# MAPE-CUN-Large-016.net
KiCad netlist of a schematic drawn in EAGLE
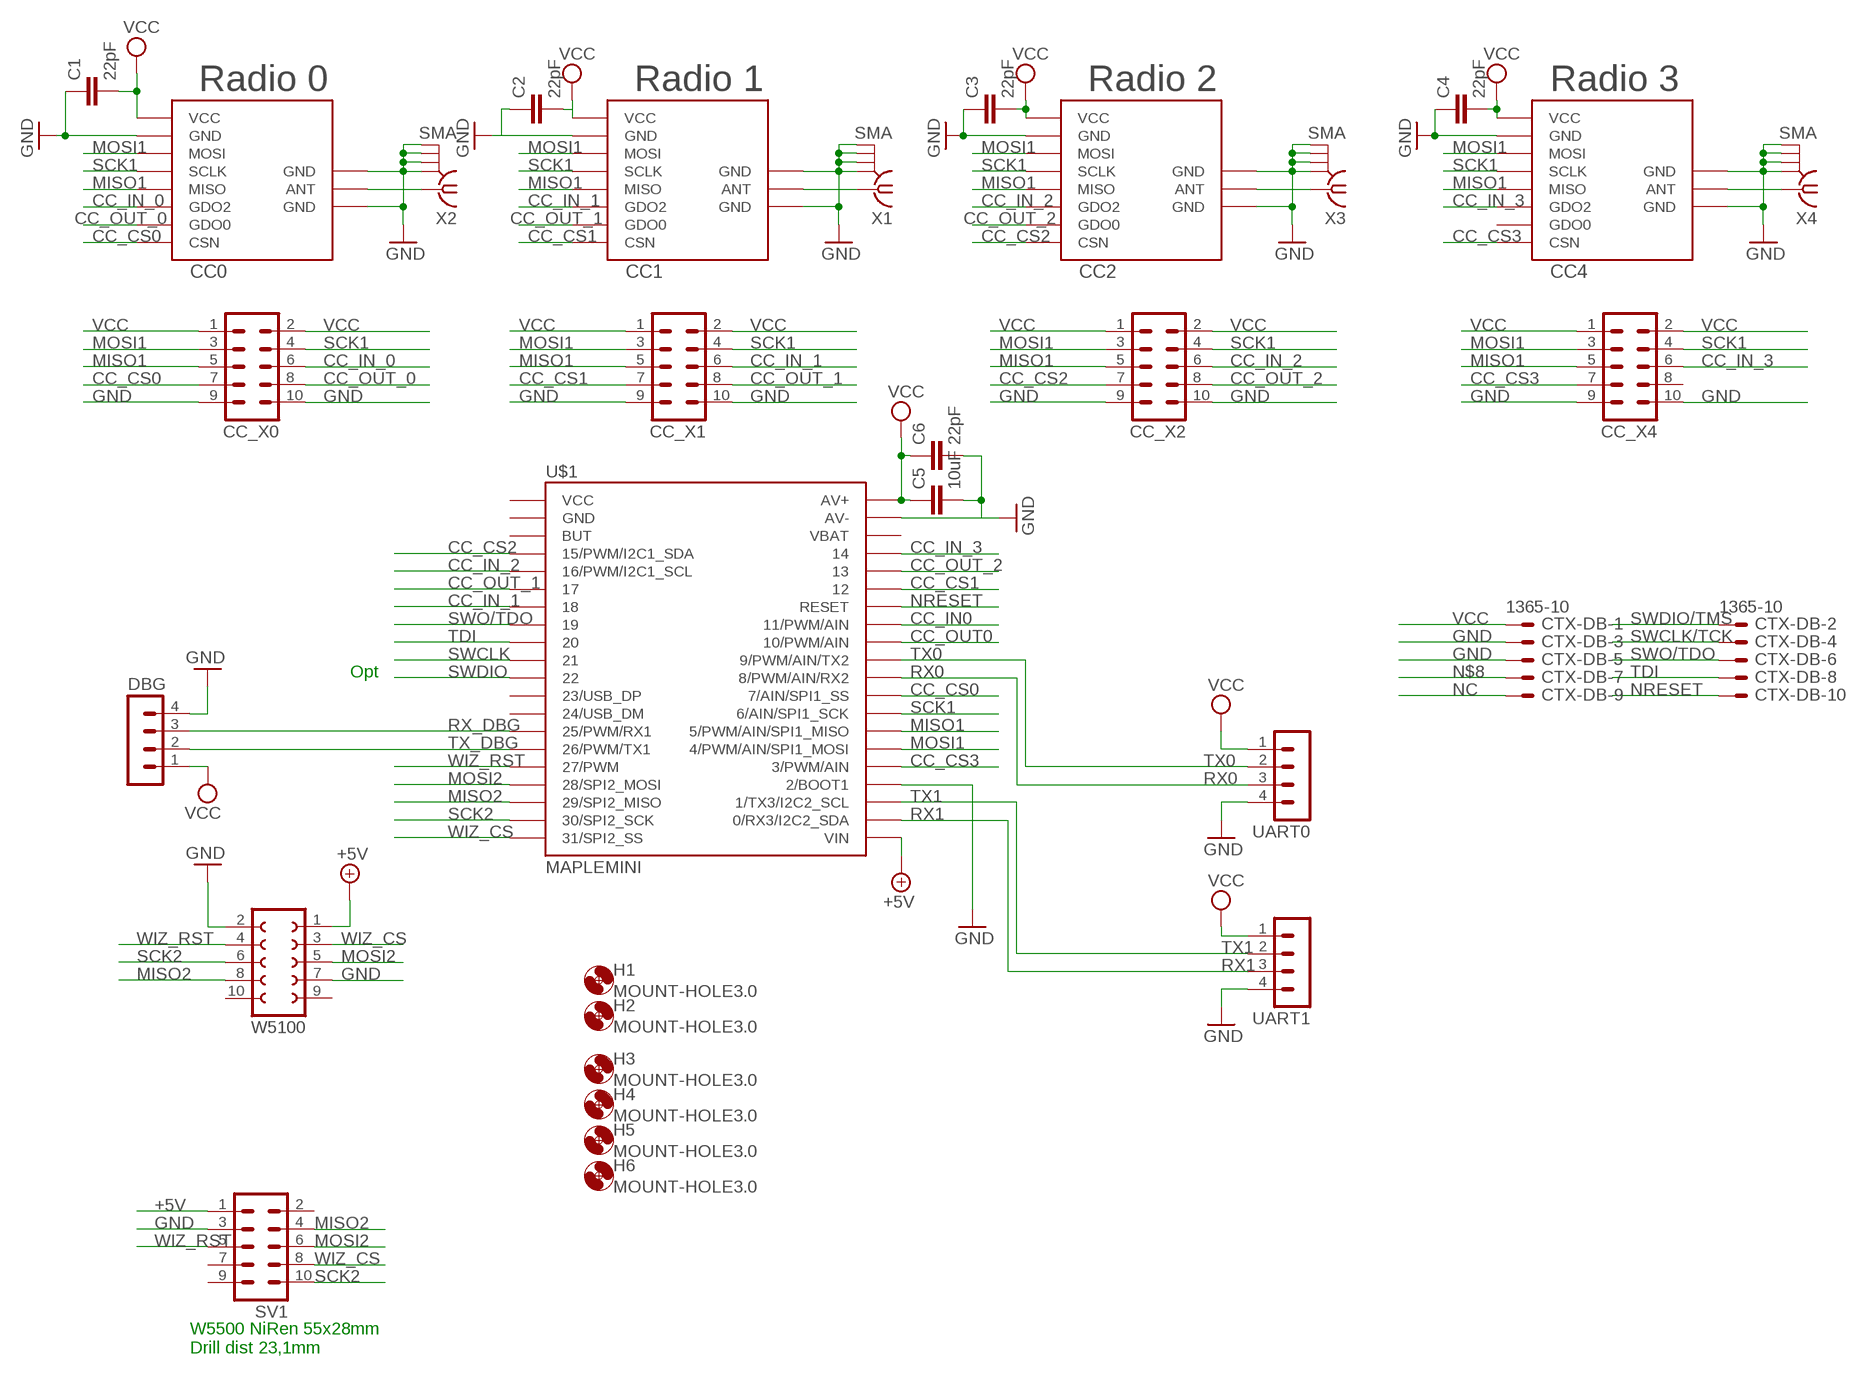
[diagram p0: schematic, sheet 1]

(export (version "E")
  (design (tool "Eeschema 10.0.6"))
  (components
    (comp (ref "C1")
      (value "22pF")
      (footprint "eagle-import:C0805")
      (libsource (lib "eagle-import") (part "C-EUC0805"))
    )
    (comp (ref "C2")
      (value "22pF")
      (footprint "eagle-import:C0805")
      (libsource (lib "eagle-import") (part "C-EUC0805"))
    )
    (comp (ref "C3")
      (value "22pF")
      (footprint "eagle-import:C0805")
      (libsource (lib "eagle-import") (part "C-EUC0805"))
    )
    (comp (ref "C4")
      (value "22pF")
      (footprint "eagle-import:C0805")
      (libsource (lib "eagle-import") (part "C-EUC0805"))
    )
    (comp (ref "C5")
      (value "10uF")
      (footprint "eagle-import:C1210")
      (libsource (lib "eagle-import") (part "C-EUC1210"))
    )
    (comp (ref "C6")
      (value "22pF")
      (footprint "eagle-import:C0805")
      (libsource (lib "eagle-import") (part "C-EUC0805"))
    )
    (comp (ref "CC0")
      (value "CC1101_MODULE1SMD")
      (footprint "eagle-import:CC1101_MODULE1_SMD")
      (libsource (lib "eagle-import") (part "CC1101_MODULE1SMD"))
    )
    (comp (ref "CC1")
      (value "CC1101_MODULE1SMD")
      (footprint "eagle-import:CC1101_MODULE1_SMD")
      (libsource (lib "eagle-import") (part "CC1101_MODULE1SMD"))
    )
    (comp (ref "CC2")
      (value "CC1101_MODULE1SMD")
      (footprint "eagle-import:CC1101_MODULE1_SMD")
      (libsource (lib "eagle-import") (part "CC1101_MODULE1SMD"))
    )
    (comp (ref "CC4")
      (value "CC1101_MODULE1SMD")
      (footprint "eagle-import:CC1101_MODULE1_SMD")
      (libsource (lib "eagle-import") (part "CC1101_MODULE1SMD"))
    )
    (comp (ref "CC_X0")
      (value "MA05-2")
      (footprint "eagle-import:MA05-2")
      (libsource (lib "eagle-import") (part "MA05-2"))
    )
    (comp (ref "CC_X1")
      (value "MA05-2")
      (footprint "eagle-import:MA05-2")
      (libsource (lib "eagle-import") (part "MA05-2"))
    )
    (comp (ref "CC_X2")
      (value "MA05-2")
      (footprint "eagle-import:MA05-2")
      (libsource (lib "eagle-import") (part "MA05-2"))
    )
    (comp (ref "CC_X4")
      (value "MA05-2")
      (footprint "eagle-import:MA05-2")
      (libsource (lib "eagle-import") (part "MA05-2"))
    )
    (comp (ref "CTX-DB")
      (value "1365-10")
      (footprint "eagle-import:1365-10")
      (libsource (lib "eagle-import") (part "1365-10"))
    )
    (comp (ref "DBG")
      (value "MA04-1")
      (footprint "eagle-import:MA04-1")
      (libsource (lib "eagle-import") (part "MA04-1"))
    )
    (comp (ref "H1")
      (value "MOUNT-HOLE3.0")
      (footprint "eagle-import:3,0")
      (libsource (lib "eagle-import") (part "MOUNT-HOLE3.0"))
    )
    (comp (ref "H2")
      (value "MOUNT-HOLE3.0")
      (footprint "eagle-import:3,0")
      (libsource (lib "eagle-import") (part "MOUNT-HOLE3.0"))
    )
    (comp (ref "H3")
      (value "MOUNT-HOLE3.0")
      (footprint "eagle-import:3,0")
      (libsource (lib "eagle-import") (part "MOUNT-HOLE3.0"))
    )
    (comp (ref "H4")
      (value "MOUNT-HOLE3.0")
      (footprint "eagle-import:3,0")
      (libsource (lib "eagle-import") (part "MOUNT-HOLE3.0"))
    )
    (comp (ref "H5")
      (value "MOUNT-HOLE3.0")
      (footprint "eagle-import:3,0")
      (libsource (lib "eagle-import") (part "MOUNT-HOLE3.0"))
    )
    (comp (ref "H6")
      (value "MOUNT-HOLE3.0")
      (footprint "eagle-import:3,0")
      (libsource (lib "eagle-import") (part "MOUNT-HOLE3.0"))
    )
    (comp (ref "SV1")
      (value "MA05-2")
      (footprint "eagle-import:MA05-2")
      (libsource (lib "eagle-import") (part "MA05-2"))
    )
    (comp (ref "U$1")
      (value "MAPLEMINI")
      (footprint "eagle-import:20-DIP")
      (libsource (lib "eagle-import") (part "MAPLEMINI"))
    )
    (comp (ref "UART0")
      (value "MA04-1")
      (footprint "eagle-import:MA04-1")
      (libsource (lib "eagle-import") (part "MA04-1"))
    )
    (comp (ref "UART1")
      (value "MA04-1")
      (footprint "eagle-import:MA04-1")
      (libsource (lib "eagle-import") (part "MA04-1"))
    )
    (comp (ref "W5100")
      (value "FE05-2")
      (footprint "eagle-import:FE05-2")
      (libsource (lib "eagle-import") (part "FE05-2"))
    )
    (comp (ref "X1")
      (value "SMA")
      (footprint "eagle-import:SMA")
      (libsource (lib "eagle-import") (part "SMA"))
    )
    (comp (ref "X2")
      (value "SMA")
      (footprint "eagle-import:SMA")
      (libsource (lib "eagle-import") (part "SMA"))
    )
    (comp (ref "X3")
      (value "SMA")
      (footprint "eagle-import:SMA")
      (libsource (lib "eagle-import") (part "SMA"))
    )
    (comp (ref "X4")
      (value "SMA")
      (footprint "eagle-import:SMA")
      (libsource (lib "eagle-import") (part "SMA"))
    )
  )
  (nets
    (net (code "1") (name "+5V") (class "Default")
      (node (ref "SV1") (pin "1") (pinfunction "1_1") (pintype "passive"))
      (node (ref "U$1") (pin "21") (pinfunction "VIN_21") (pintype "bidirectional"))
      (node (ref "W5100") (pin "1") (pinfunction "1_1") (pintype "passive"))
    )
    (net (code "2") (name "/CC_CS0") (class "Default")
      (node (ref "CC0") (pin "CSN") (pinfunction "CSN_CSN") (pintype "bidirectional"))
      (node (ref "CC_X0") (pin "7") (pinfunction "7_7") (pintype "passive"))
      (node (ref "U$1") (pin "29") (pinfunction "7/AIN/SPI1_SS_29") (pintype "bidirectional"))
    )
    (net (code "3") (name "/CC_CS1") (class "Default")
      (node (ref "CC1") (pin "CSN") (pinfunction "CSN_CSN") (pintype "bidirectional"))
      (node (ref "CC_X1") (pin "7") (pinfunction "7_7") (pintype "passive"))
      (node (ref "U$1") (pin "35") (pinfunction "12_35") (pintype "bidirectional"))
    )
    (net (code "4") (name "/CC_CS2") (class "Default")
      (node (ref "CC2") (pin "CSN") (pinfunction "CSN_CSN") (pintype "bidirectional"))
      (node (ref "CC_X2") (pin "7") (pinfunction "7_7") (pintype "passive"))
      (node (ref "U$1") (pin "4") (pinfunction "15/PWM/I2C1_SDA_4") (pintype "bidirectional"))
    )
    (net (code "5") (name "/CC_CS3") (class "Default")
      (node (ref "CC4") (pin "CSN") (pinfunction "CSN_CSN") (pintype "bidirectional"))
      (node (ref "CC_X4") (pin "7") (pinfunction "7_7") (pintype "passive"))
      (node (ref "U$1") (pin "25") (pinfunction "3/PWM/AIN_25") (pintype "bidirectional"))
    )
    (net (code "6") (name "/CC_IN0") (class "Default")
      (node (ref "U$1") (pin "33") (pinfunction "11/PWM/AIN_33") (pintype "bidirectional"))
    )
    (net (code "7") (name "/CC_IN_0") (class "Default")
      (node (ref "CC0") (pin "GDO2") (pinfunction "GDO2_GDO2") (pintype "bidirectional"))
      (node (ref "CC_X0") (pin "6") (pinfunction "6_6") (pintype "passive"))
    )
    (net (code "8") (name "/CC_IN_1") (class "Default")
      (node (ref "CC1") (pin "GDO2") (pinfunction "GDO2_GDO2") (pintype "bidirectional"))
      (node (ref "CC_X1") (pin "6") (pinfunction "6_6") (pintype "passive"))
      (node (ref "U$1") (pin "7") (pinfunction "18_7") (pintype "bidirectional"))
    )
    (net (code "9") (name "/CC_IN_2") (class "Default")
      (node (ref "CC2") (pin "GDO2") (pinfunction "GDO2_GDO2") (pintype "bidirectional"))
      (node (ref "CC_X2") (pin "6") (pinfunction "6_6") (pintype "passive"))
      (node (ref "U$1") (pin "5") (pinfunction "16/PWM/I2C1_SCL_5") (pintype "bidirectional"))
    )
    (net (code "10") (name "/CC_IN_3") (class "Default")
      (node (ref "CC4") (pin "GDO2") (pinfunction "GDO2_GDO2") (pintype "bidirectional"))
      (node (ref "CC_X4") (pin "6") (pinfunction "6_6") (pintype "passive"))
      (node (ref "U$1") (pin "37") (pinfunction "14_37") (pintype "bidirectional"))
    )
    (net (code "11") (name "/CC_OUT0") (class "Default")
      (node (ref "U$1") (pin "32") (pinfunction "10/PWM/AIN_32") (pintype "bidirectional"))
    )
    (net (code "12") (name "/CC_OUT_0") (class "Default")
      (node (ref "CC0") (pin "GDO0") (pinfunction "GDO0_GDO0") (pintype "bidirectional"))
      (node (ref "CC_X0") (pin "8") (pinfunction "8_8") (pintype "passive"))
    )
    (net (code "13") (name "/CC_OUT_1") (class "Default")
      (node (ref "CC1") (pin "GDO0") (pinfunction "GDO0_GDO0") (pintype "bidirectional"))
      (node (ref "CC_X1") (pin "8") (pinfunction "8_8") (pintype "passive"))
      (node (ref "U$1") (pin "6") (pinfunction "17_6") (pintype "bidirectional"))
    )
    (net (code "14") (name "/CC_OUT_2") (class "Default")
      (node (ref "CC2") (pin "GDO0") (pinfunction "GDO0_GDO0") (pintype "bidirectional"))
      (node (ref "CC_X2") (pin "8") (pinfunction "8_8") (pintype "passive"))
      (node (ref "U$1") (pin "36") (pinfunction "13_36") (pintype "bidirectional"))
    )
    (net (code "15") (name "/MISO1") (class "Default")
      (node (ref "CC0") (pin "MISO") (pinfunction "MISO_MISO") (pintype "bidirectional"))
      (node (ref "CC1") (pin "MISO") (pinfunction "MISO_MISO") (pintype "bidirectional"))
      (node (ref "CC2") (pin "MISO") (pinfunction "MISO_MISO") (pintype "bidirectional"))
      (node (ref "CC4") (pin "MISO") (pinfunction "MISO_MISO") (pintype "bidirectional"))
      (node (ref "CC_X0") (pin "5") (pinfunction "5_5") (pintype "passive"))
      (node (ref "CC_X1") (pin "5") (pinfunction "5_5") (pintype "passive"))
      (node (ref "CC_X2") (pin "5") (pinfunction "5_5") (pintype "passive"))
      (node (ref "CC_X4") (pin "5") (pinfunction "5_5") (pintype "passive"))
      (node (ref "U$1") (pin "27") (pinfunction "5/PWM/AIN/SPI1_MISO_27") (pintype "bidirectional"))
    )
    (net (code "16") (name "/MISO2") (class "Default")
      (node (ref "SV1") (pin "4") (pinfunction "4_4") (pintype "passive"))
      (node (ref "U$1") (pin "18") (pinfunction "29/SPI2_MISO_18") (pintype "bidirectional"))
      (node (ref "W5100") (pin "8") (pinfunction "8_8") (pintype "passive"))
    )
    (net (code "17") (name "/MOSI1") (class "Default")
      (node (ref "CC0") (pin "MOSI") (pinfunction "MOSI_MOSI") (pintype "bidirectional"))
      (node (ref "CC1") (pin "MOSI") (pinfunction "MOSI_MOSI") (pintype "bidirectional"))
      (node (ref "CC2") (pin "MOSI") (pinfunction "MOSI_MOSI") (pintype "bidirectional"))
      (node (ref "CC4") (pin "MOSI") (pinfunction "MOSI_MOSI") (pintype "bidirectional"))
      (node (ref "CC_X0") (pin "3") (pinfunction "3_3") (pintype "passive"))
      (node (ref "CC_X1") (pin "3") (pinfunction "3_3") (pintype "passive"))
      (node (ref "CC_X2") (pin "3") (pinfunction "3_3") (pintype "passive"))
      (node (ref "CC_X4") (pin "3") (pinfunction "3_3") (pintype "passive"))
      (node (ref "U$1") (pin "26") (pinfunction "4/PWM/AIN/SPI1_MOSI_26") (pintype "bidirectional"))
    )
    (net (code "18") (name "/MOSI2") (class "Default")
      (node (ref "SV1") (pin "6") (pinfunction "6_6") (pintype "passive"))
      (node (ref "U$1") (pin "17") (pinfunction "28/SPI2_MOSI_17") (pintype "bidirectional"))
      (node (ref "W5100") (pin "5") (pinfunction "5_5") (pintype "passive"))
    )
    (net (code "19") (name "/N$8") (class "Default")
      (node (ref "CTX-DB") (pin "7") (pinfunction "S_7") (pintype "passive"))
    )
    (net (code "20") (name "/NC") (class "Default")
      (node (ref "CTX-DB") (pin "9") (pinfunction "S_9") (pintype "passive"))
    )
    (net (code "21") (name "/NRESET") (class "Default")
      (node (ref "CTX-DB") (pin "10") (pinfunction "S_10") (pintype "passive"))
      (node (ref "U$1") (pin "34") (pinfunction "RESET_34") (pintype "bidirectional"))
    )
    (net (code "22") (name "/RX0") (class "Default")
      (node (ref "U$1") (pin "30") (pinfunction "8/PWM/AIN/RX2_30") (pintype "bidirectional"))
      (node (ref "UART0") (pin "3") (pinfunction "3_3") (pintype "passive"))
    )
    (net (code "23") (name "/RX1") (class "Default")
      (node (ref "U$1") (pin "22") (pinfunction "0/RX3/I2C2_SDA_22") (pintype "bidirectional"))
      (node (ref "UART1") (pin "3") (pinfunction "3_3") (pintype "passive"))
    )
    (net (code "24") (name "/RX_DBG") (class "Default")
      (node (ref "DBG") (pin "3") (pinfunction "3_3") (pintype "passive"))
      (node (ref "U$1") (pin "14") (pinfunction "25/PWM/RX1_14") (pintype "bidirectional"))
    )
    (net (code "25") (name "/SCK1") (class "Default")
      (node (ref "CC0") (pin "SCLK") (pinfunction "SCLK_SCLK") (pintype "bidirectional"))
      (node (ref "CC1") (pin "SCLK") (pinfunction "SCLK_SCLK") (pintype "bidirectional"))
      (node (ref "CC2") (pin "SCLK") (pinfunction "SCLK_SCLK") (pintype "bidirectional"))
      (node (ref "CC4") (pin "SCLK") (pinfunction "SCLK_SCLK") (pintype "bidirectional"))
      (node (ref "CC_X0") (pin "4") (pinfunction "4_4") (pintype "passive"))
      (node (ref "CC_X1") (pin "4") (pinfunction "4_4") (pintype "passive"))
      (node (ref "CC_X2") (pin "4") (pinfunction "4_4") (pintype "passive"))
      (node (ref "CC_X4") (pin "4") (pinfunction "4_4") (pintype "passive"))
      (node (ref "U$1") (pin "28") (pinfunction "6/AIN/SPI1_SCK_28") (pintype "bidirectional"))
    )
    (net (code "26") (name "/SCK2") (class "Default")
      (node (ref "SV1") (pin "10") (pinfunction "10_10") (pintype "passive"))
      (node (ref "U$1") (pin "19") (pinfunction "30/SPI2_SCK_19") (pintype "bidirectional"))
      (node (ref "W5100") (pin "6") (pinfunction "6_6") (pintype "passive"))
    )
    (net (code "27") (name "/SWCLK") (class "Default")
      (node (ref "U$1") (pin "10") (pinfunction "21_10") (pintype "bidirectional"))
    )
    (net (code "28") (name "/SWCLK{slash}TCK") (class "Default")
      (node (ref "CTX-DB") (pin "4") (pinfunction "S_4") (pintype "passive"))
    )
    (net (code "29") (name "/SWDIO") (class "Default")
      (node (ref "U$1") (pin "11") (pinfunction "22_11") (pintype "bidirectional"))
    )
    (net (code "30") (name "/SWDIO{slash}TMS") (class "Default")
      (node (ref "CTX-DB") (pin "2") (pinfunction "S_2") (pintype "passive"))
    )
    (net (code "31") (name "/SWO{slash}TDO") (class "Default")
      (node (ref "CTX-DB") (pin "6") (pinfunction "S_6") (pintype "passive"))
      (node (ref "U$1") (pin "8") (pinfunction "19_8") (pintype "bidirectional"))
    )
    (net (code "32") (name "/TDI") (class "Default")
      (node (ref "CTX-DB") (pin "8") (pinfunction "S_8") (pintype "passive"))
      (node (ref "U$1") (pin "9") (pinfunction "20_9") (pintype "bidirectional"))
    )
    (net (code "33") (name "/TX0") (class "Default")
      (node (ref "U$1") (pin "31") (pinfunction "9/PWM/AIN/TX2_31") (pintype "bidirectional"))
      (node (ref "UART0") (pin "2") (pinfunction "2_2") (pintype "passive"))
    )
    (net (code "34") (name "/TX1") (class "Default")
      (node (ref "U$1") (pin "23") (pinfunction "1/TX3/I2C2_SCL_23") (pintype "bidirectional"))
      (node (ref "UART1") (pin "2") (pinfunction "2_2") (pintype "passive"))
    )
    (net (code "35") (name "/TX_DBG") (class "Default")
      (node (ref "DBG") (pin "2") (pinfunction "2_2") (pintype "passive"))
      (node (ref "U$1") (pin "15") (pinfunction "26/PWM/TX1_15") (pintype "bidirectional"))
    )
    (net (code "36") (name "/WIZ_CS") (class "Default")
      (node (ref "SV1") (pin "8") (pinfunction "8_8") (pintype "passive"))
      (node (ref "U$1") (pin "20") (pinfunction "31/SPI2_SS_20") (pintype "bidirectional"))
      (node (ref "W5100") (pin "3") (pinfunction "3_3") (pintype "passive"))
    )
    (net (code "37") (name "/WIZ_RST") (class "Default")
      (node (ref "SV1") (pin "5") (pinfunction "5_5") (pintype "passive"))
      (node (ref "U$1") (pin "16") (pinfunction "27/PWM_16") (pintype "bidirectional"))
      (node (ref "W5100") (pin "4") (pinfunction "4_4") (pintype "passive"))
    )
    (net (code "38") (name "GND") (class "Default")
      (node (ref "C1") (pin "1") (pinfunction "1_1") (pintype "passive"))
      (node (ref "C2") (pin "1") (pinfunction "1_1") (pintype "passive"))
      (node (ref "C3") (pin "1") (pinfunction "1_1") (pintype "passive"))
      (node (ref "C4") (pin "1") (pinfunction "1_1") (pintype "passive"))
      (node (ref "C5") (pin "2") (pinfunction "2_2") (pintype "passive"))
      (node (ref "C6") (pin "2") (pinfunction "2_2") (pintype "passive"))
      (node (ref "CC0") (pin "GND@0") (pinfunction "GND_GND@0") (pintype "power_in"))
      (node (ref "CC0") (pin "GND@1") (pinfunction "GND_GND@1") (pintype "power_in"))
      (node (ref "CC0") (pin "GND@2") (pinfunction "GND_GND@2") (pintype "power_in"))
      (node (ref "CC1") (pin "GND@0") (pinfunction "GND_GND@0") (pintype "power_in"))
      (node (ref "CC1") (pin "GND@1") (pinfunction "GND_GND@1") (pintype "power_in"))
      (node (ref "CC1") (pin "GND@2") (pinfunction "GND_GND@2") (pintype "power_in"))
      (node (ref "CC2") (pin "GND@0") (pinfunction "GND_GND@0") (pintype "power_in"))
      (node (ref "CC2") (pin "GND@1") (pinfunction "GND_GND@1") (pintype "power_in"))
      (node (ref "CC2") (pin "GND@2") (pinfunction "GND_GND@2") (pintype "power_in"))
      (node (ref "CC4") (pin "GND@0") (pinfunction "GND_GND@0") (pintype "power_in"))
      (node (ref "CC4") (pin "GND@1") (pinfunction "GND_GND@1") (pintype "power_in"))
      (node (ref "CC4") (pin "GND@2") (pinfunction "GND_GND@2") (pintype "power_in"))
      (node (ref "CC_X0") (pin "10") (pinfunction "10_10") (pintype "passive"))
      (node (ref "CC_X0") (pin "9") (pinfunction "9_9") (pintype "passive"))
      (node (ref "CC_X1") (pin "10") (pinfunction "10_10") (pintype "passive"))
      (node (ref "CC_X1") (pin "9") (pinfunction "9_9") (pintype "passive"))
      (node (ref "CC_X2") (pin "10") (pinfunction "10_10") (pintype "passive"))
      (node (ref "CC_X2") (pin "9") (pinfunction "9_9") (pintype "passive"))
      (node (ref "CC_X4") (pin "10") (pinfunction "10_10") (pintype "passive"))
      (node (ref "CC_X4") (pin "9") (pinfunction "9_9") (pintype "passive"))
      (node (ref "CTX-DB") (pin "3") (pinfunction "S_3") (pintype "passive"))
      (node (ref "CTX-DB") (pin "5") (pinfunction "S_5") (pintype "passive"))
      (node (ref "DBG") (pin "4") (pinfunction "4_4") (pintype "passive"))
      (node (ref "SV1") (pin "3") (pinfunction "3_3") (pintype "passive"))
      (node (ref "U$1") (pin "24") (pinfunction "2/BOOT1_24") (pintype "bidirectional"))
      (node (ref "U$1") (pin "39") (pinfunction "AV-_39") (pintype "bidirectional"))
      (node (ref "UART0") (pin "4") (pinfunction "4_4") (pintype "passive"))
      (node (ref "UART1") (pin "4") (pinfunction "4_4") (pintype "passive"))
      (node (ref "W5100") (pin "2") (pinfunction "2_2") (pintype "passive"))
      (node (ref "W5100") (pin "7") (pinfunction "7_7") (pintype "passive"))
      (node (ref "X1") (pin "GND@1") (pinfunction "2_GND@1") (pintype "passive"))
      (node (ref "X1") (pin "GND@2") (pinfunction "3_GND@2") (pintype "passive"))
      (node (ref "X1") (pin "GND@3") (pinfunction "4_GND@3") (pintype "passive"))
      (node (ref "X1") (pin "GND@4") (pinfunction "5_GND@4") (pintype "passive"))
      (node (ref "X2") (pin "GND@1") (pinfunction "2_GND@1") (pintype "passive"))
      (node (ref "X2") (pin "GND@2") (pinfunction "3_GND@2") (pintype "passive"))
      (node (ref "X2") (pin "GND@3") (pinfunction "4_GND@3") (pintype "passive"))
      (node (ref "X2") (pin "GND@4") (pinfunction "5_GND@4") (pintype "passive"))
      (node (ref "X3") (pin "GND@1") (pinfunction "2_GND@1") (pintype "passive"))
      (node (ref "X3") (pin "GND@2") (pinfunction "3_GND@2") (pintype "passive"))
      (node (ref "X3") (pin "GND@3") (pinfunction "4_GND@3") (pintype "passive"))
      (node (ref "X3") (pin "GND@4") (pinfunction "5_GND@4") (pintype "passive"))
      (node (ref "X4") (pin "GND@1") (pinfunction "2_GND@1") (pintype "passive"))
      (node (ref "X4") (pin "GND@2") (pinfunction "3_GND@2") (pintype "passive"))
      (node (ref "X4") (pin "GND@3") (pinfunction "4_GND@3") (pintype "passive"))
      (node (ref "X4") (pin "GND@4") (pinfunction "5_GND@4") (pintype "passive"))
    )
    (net (code "39") (name "Net-(CC0-PadANT)") (class "Default")
      (node (ref "CC0") (pin "ANT") (pinfunction "ANT_ANT") (pintype "output"))
      (node (ref "X2") (pin "1") (pinfunction "1_1") (pintype "passive"))
    )
    (net (code "40") (name "Net-(CC1-PadANT)") (class "Default")
      (node (ref "CC1") (pin "ANT") (pinfunction "ANT_ANT") (pintype "output"))
      (node (ref "X1") (pin "1") (pinfunction "1_1") (pintype "passive"))
    )
    (net (code "41") (name "Net-(CC2-PadANT)") (class "Default")
      (node (ref "CC2") (pin "ANT") (pinfunction "ANT_ANT") (pintype "output"))
      (node (ref "X3") (pin "1") (pinfunction "1_1") (pintype "passive"))
    )
    (net (code "42") (name "Net-(CC4-PadANT)") (class "Default")
      (node (ref "CC4") (pin "ANT") (pinfunction "ANT_ANT") (pintype "output"))
      (node (ref "X4") (pin "1") (pinfunction "1_1") (pintype "passive"))
    )
    (net (code "43") (name "VCC") (class "Default")
      (node (ref "C1") (pin "2") (pinfunction "2_2") (pintype "passive"))
      (node (ref "C2") (pin "2") (pinfunction "2_2") (pintype "passive"))
      (node (ref "C3") (pin "2") (pinfunction "2_2") (pintype "passive"))
      (node (ref "C4") (pin "2") (pinfunction "2_2") (pintype "passive"))
      (node (ref "C5") (pin "1") (pinfunction "1_1") (pintype "passive"))
      (node (ref "C6") (pin "1") (pinfunction "1_1") (pintype "passive"))
      (node (ref "CC0") (pin "VCC") (pinfunction "VCC_VCC") (pintype "power_in"))
      (node (ref "CC1") (pin "VCC") (pinfunction "VCC_VCC") (pintype "power_in"))
      (node (ref "CC2") (pin "VCC") (pinfunction "VCC_VCC") (pintype "power_in"))
      (node (ref "CC4") (pin "VCC") (pinfunction "VCC_VCC") (pintype "power_in"))
      (node (ref "CC_X0") (pin "1") (pinfunction "1_1") (pintype "passive"))
      (node (ref "CC_X0") (pin "2") (pinfunction "2_2") (pintype "passive"))
      (node (ref "CC_X1") (pin "1") (pinfunction "1_1") (pintype "passive"))
      (node (ref "CC_X1") (pin "2") (pinfunction "2_2") (pintype "passive"))
      (node (ref "CC_X2") (pin "1") (pinfunction "1_1") (pintype "passive"))
      (node (ref "CC_X2") (pin "2") (pinfunction "2_2") (pintype "passive"))
      (node (ref "CC_X4") (pin "1") (pinfunction "1_1") (pintype "passive"))
      (node (ref "CC_X4") (pin "2") (pinfunction "2_2") (pintype "passive"))
      (node (ref "CTX-DB") (pin "1") (pinfunction "S_1") (pintype "passive"))
      (node (ref "DBG") (pin "1") (pinfunction "1_1") (pintype "passive"))
      (node (ref "U$1") (pin "40") (pinfunction "AV+_40") (pintype "bidirectional"))
      (node (ref "UART0") (pin "1") (pinfunction "1_1") (pintype "passive"))
      (node (ref "UART1") (pin "1") (pinfunction "1_1") (pintype "passive"))
    )
    (net (code "44") (name "unconnected-(CC4-PadGDO0)") (class "Default")
      (node (ref "CC4") (pin "GDO0") (pinfunction "GDO0_GDO0") (pintype "bidirectional"))
    )
    (net (code "45") (name "unconnected-(CC_X4-Pad8)") (class "Default")
      (node (ref "CC_X4") (pin "8") (pinfunction "8_8") (pintype "passive"))
    )
    (net (code "46") (name "unconnected-(SV1-Pad2)") (class "Default")
      (node (ref "SV1") (pin "2") (pinfunction "2_2") (pintype "passive"))
    )
    (net (code "47") (name "unconnected-(SV1-Pad7)") (class "Default")
      (node (ref "SV1") (pin "7") (pinfunction "7_7") (pintype "passive"))
    )
    (net (code "48") (name "unconnected-(SV1-Pad9)") (class "Default")
      (node (ref "SV1") (pin "9") (pinfunction "9_9") (pintype "passive"))
    )
    (net (code "49") (name "unconnected-(U$1-23{slash}USB_DP-Pad12)") (class "Default")
      (node (ref "U$1") (pin "12") (pinfunction "23/USB_DP_12") (pintype "bidirectional"))
    )
    (net (code "50") (name "unconnected-(U$1-24{slash}USB_DM-Pad13)") (class "Default")
      (node (ref "U$1") (pin "13") (pinfunction "24/USB_DM_13") (pintype "bidirectional"))
    )
    (net (code "51") (name "unconnected-(U$1-BUT-Pad3)") (class "Default")
      (node (ref "U$1") (pin "3") (pinfunction "BUT_3") (pintype "bidirectional"))
    )
    (net (code "52") (name "unconnected-(U$1-GND-Pad2)") (class "Default")
      (node (ref "U$1") (pin "2") (pinfunction "GND_2") (pintype "bidirectional"))
    )
    (net (code "53") (name "unconnected-(U$1-VBAT-Pad38)") (class "Default")
      (node (ref "U$1") (pin "38") (pinfunction "VBAT_38") (pintype "bidirectional"))
    )
    (net (code "54") (name "unconnected-(U$1-VCC-Pad1)") (class "Default")
      (node (ref "U$1") (pin "1") (pinfunction "VCC_1") (pintype "bidirectional"))
    )
    (net (code "55") (name "unconnected-(W5100-Pad9)") (class "Default")
      (node (ref "W5100") (pin "9") (pinfunction "9_9") (pintype "passive"))
    )
    (net (code "56") (name "unconnected-(W5100-Pad10)") (class "Default")
      (node (ref "W5100") (pin "10") (pinfunction "10_10") (pintype "passive"))
    )
  )
)
